# test2.net
KiCad netlist of a schematic drawn in Altium Designer
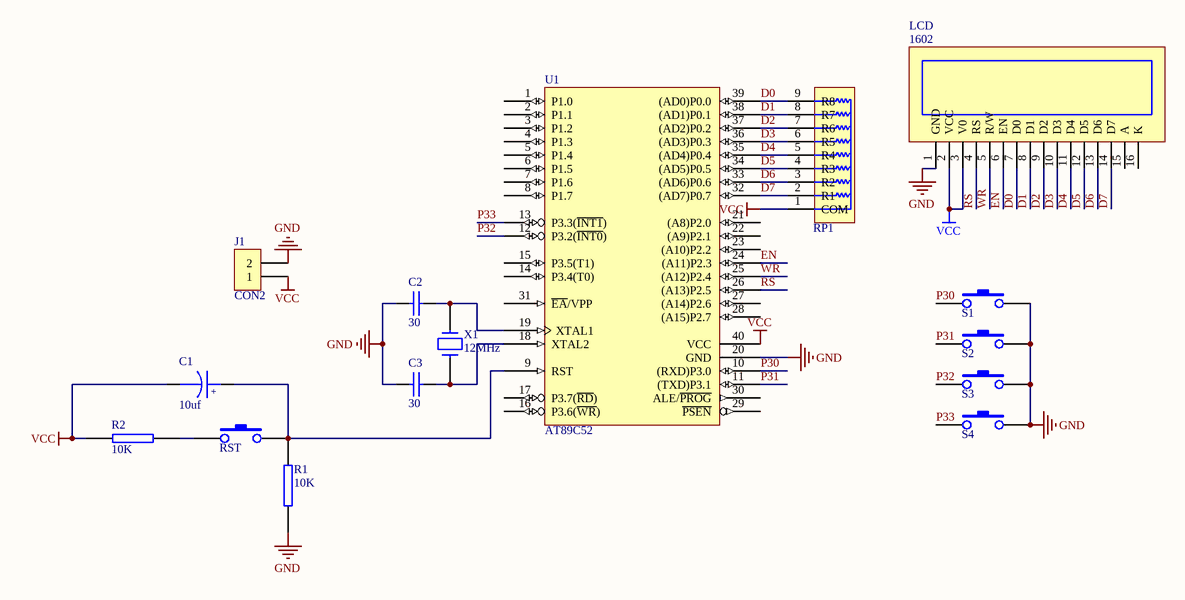
[diagram p0: test2.SchDoc]

(export (version "E")
  (design (tool "Eeschema 10.0.6"))
  (components
    (comp (ref "C1")
      (value "10uf")
      (footprint "C_SMT-5*5")
      (description "Capacitor")
      (libsource (lib "xinweidz") (part "电解电容"))
    )
    (comp (ref "C2")
      (value "30")
      (footprint "C0805")
      (description "Capacitor")
      (libsource (lib "*") (part "CAP"))
    )
    (comp (ref "C3")
      (value "30")
      (footprint "C0805")
      (description "Capacitor")
      (libsource (lib "*") (part "CAP"))
    )
    (comp (ref "J1")
      (value "CON2")
      (footprint "TC2")
      (description "Connector")
      (libsource (lib "51单片机最小系统.PcbDoc") (part "CON2"))
    )
    (comp (ref "LCD") (value "1602") (footprint "LCD1602") (libsource (lib "*") (part "LCM1602")))
    (comp (ref "R1") (value "10K") (footprint "C0805") (libsource (lib "*") (part "RES2")))
    (comp (ref "R2") (value "10K") (footprint "C0805") (libsource (lib "*") (part "RES2")))
    (comp (ref "RP1") (value "103") (footprint "R-9PIN") (libsource (lib "*") (part "RP8")))
    (comp (ref "RST")
      (value "SW-PB")
      (footprint "ANJIAN")
      (libsource (lib "51单片机最小系统.PcbDoc") (part "SW-PB"))
    )
    (comp (ref "S1") (value "SW-PB") (footprint "ANJIAN") (libsource (lib "51单片机最小系统.PcbDoc") (part "SW-PB")))
    (comp (ref "S2") (value "SW-PB") (footprint "ANJIAN") (libsource (lib "51单片机最小系统.PcbDoc") (part "SW-PB")))
    (comp (ref "S3") (value "SW-PB") (footprint "ANJIAN") (libsource (lib "51单片机最小系统.PcbDoc") (part "SW-PB")))
    (comp (ref "S4") (value "SW-PB") (footprint "ANJIAN") (libsource (lib "51单片机最小系统.PcbDoc") (part "SW-PB")))
    (comp (ref "U1")
      (value "AT89C52")
      (footprint "JINSUOZUO")
      (description "8-Bit Microcontroller with 4K Flash ROM")
      (libsource (lib "51单片机最小系统.PcbDoc") (part "AT89C51"))
    )
    (comp (ref "X1")
      (value "12MHz")
      (footprint "XTAL1")
      (description "Crystal")
      (libsource (lib "*") (part "CRYSTAL"))
    )
  )
  (nets
    (net (code "1") (name "/D0") (class "Default")
      (node (ref "LCD") (pin "7") (pinfunction "D0_7") (pintype "passive"))
      (node (ref "RP1") (pin "9") (pinfunction "R8_9") (pintype "passive"))
      (node (ref "U1") (pin "39") (pinfunction "(AD0)P0.0_39") (pintype "bidirectional"))
    )
    (net (code "2") (name "/D1") (class "Default")
      (node (ref "LCD") (pin "8") (pinfunction "D1_8") (pintype "passive"))
      (node (ref "RP1") (pin "8") (pinfunction "R7_8") (pintype "passive"))
      (node (ref "U1") (pin "38") (pinfunction "(AD1)P0.1_38") (pintype "bidirectional"))
    )
    (net (code "3") (name "/D2") (class "Default")
      (node (ref "LCD") (pin "9") (pinfunction "D2_9") (pintype "passive"))
      (node (ref "RP1") (pin "7") (pinfunction "R6_7") (pintype "passive"))
      (node (ref "U1") (pin "37") (pinfunction "(AD2)P0.2_37") (pintype "bidirectional"))
    )
    (net (code "4") (name "/D3") (class "Default")
      (node (ref "LCD") (pin "10") (pinfunction "D3_10") (pintype "passive"))
      (node (ref "RP1") (pin "6") (pinfunction "R5_6") (pintype "passive"))
      (node (ref "U1") (pin "36") (pinfunction "(AD3)P0.3_36") (pintype "bidirectional"))
    )
    (net (code "5") (name "/D4") (class "Default")
      (node (ref "LCD") (pin "11") (pinfunction "D4_11") (pintype "passive"))
      (node (ref "RP1") (pin "5") (pinfunction "R4_5") (pintype "passive"))
      (node (ref "U1") (pin "35") (pinfunction "(AD4)P0.4_35") (pintype "bidirectional"))
    )
    (net (code "6") (name "/D5") (class "Default")
      (node (ref "LCD") (pin "12") (pinfunction "D5_12") (pintype "passive"))
      (node (ref "RP1") (pin "4") (pinfunction "R3_4") (pintype "passive"))
      (node (ref "U1") (pin "34") (pinfunction "(AD5)P0.5_34") (pintype "bidirectional"))
    )
    (net (code "7") (name "/D6") (class "Default")
      (node (ref "LCD") (pin "13") (pinfunction "D6_13") (pintype "passive"))
      (node (ref "RP1") (pin "3") (pinfunction "R2_3") (pintype "passive"))
      (node (ref "U1") (pin "33") (pinfunction "(AD6)P0.6_33") (pintype "bidirectional"))
    )
    (net (code "8") (name "/D7") (class "Default")
      (node (ref "LCD") (pin "14") (pinfunction "D7_14") (pintype "passive"))
      (node (ref "RP1") (pin "2") (pinfunction "R1_2") (pintype "passive"))
      (node (ref "U1") (pin "32") (pinfunction "(AD7)P0.7_32") (pintype "bidirectional"))
    )
    (net (code "9") (name "/EN") (class "Default")
      (node (ref "LCD") (pin "6") (pinfunction "EN_6") (pintype "passive"))
      (node (ref "U1") (pin "24") (pinfunction "(A11)P2.3_24") (pintype "bidirectional"))
    )
    (net (code "10") (name "/P30") (class "Default")
      (node (ref "S1") (pin "1") (pinfunction "1_1") (pintype "passive"))
      (node (ref "U1") (pin "10") (pinfunction "(RXD)P3.0_10") (pintype "bidirectional"))
    )
    (net (code "11") (name "/P31") (class "Default")
      (node (ref "S2") (pin "1") (pinfunction "1_1") (pintype "passive"))
      (node (ref "U1") (pin "11") (pinfunction "(TXD)P3.1_11") (pintype "bidirectional"))
    )
    (net (code "12") (name "/P32") (class "Default")
      (node (ref "S3") (pin "1") (pinfunction "1_1") (pintype "passive"))
      (node (ref "U1") (pin "12") (pinfunction "P3.2(~{INT0})_12") (pintype "bidirectional"))
    )
    (net (code "13") (name "/P33") (class "Default")
      (node (ref "S4") (pin "1") (pinfunction "1_1") (pintype "passive"))
      (node (ref "U1") (pin "13") (pinfunction "P3.3(~{INT1})_13") (pintype "bidirectional"))
    )
    (net (code "14") (name "/RS") (class "Default")
      (node (ref "LCD") (pin "4") (pinfunction "RS_4") (pintype "passive"))
      (node (ref "U1") (pin "26") (pinfunction "(A13)P2.5_26") (pintype "bidirectional"))
    )
    (net (code "15") (name "/WR") (class "Default")
      (node (ref "LCD") (pin "5") (pinfunction "R/W_5") (pintype "passive"))
      (node (ref "U1") (pin "25") (pinfunction "(A12)P2.4_25") (pintype "bidirectional"))
    )
    (net (code "16") (name "GND") (class "Default")
      (node (ref "C2") (pin "2") (pinfunction "2_2") (pintype "passive"))
      (node (ref "C3") (pin "2") (pinfunction "2_2") (pintype "passive"))
      (node (ref "J1") (pin "2") (pinfunction "2_2") (pintype "passive"))
      (node (ref "LCD") (pin "1") (pinfunction "GND_1") (pintype "passive"))
      (node (ref "R1") (pin "2") (pinfunction "2_2") (pintype "passive"))
      (node (ref "S1") (pin "2") (pinfunction "2_2") (pintype "passive"))
      (node (ref "S2") (pin "2") (pinfunction "2_2") (pintype "passive"))
      (node (ref "S3") (pin "2") (pinfunction "2_2") (pintype "passive"))
      (node (ref "S4") (pin "2") (pinfunction "2_2") (pintype "passive"))
      (node (ref "U1") (pin "20") (pinfunction "GND_20") (pintype "power_in"))
    )
    (net (code "17") (name "Net-(R2-Pad2)") (class "Default")
      (node (ref "R2") (pin "2") (pinfunction "2_2") (pintype "passive"))
      (node (ref "RST") (pin "1") (pinfunction "1_1") (pintype "passive"))
    )
    (net (code "18") (name "Net-(U1-RST)") (class "Default")
      (node (ref "C1") (pin "2") (pinfunction "2_2") (pintype "passive"))
      (node (ref "R1") (pin "1") (pinfunction "1_1") (pintype "passive"))
      (node (ref "RST") (pin "2") (pinfunction "2_2") (pintype "passive"))
      (node (ref "U1") (pin "9") (pinfunction "RST_9") (pintype "input"))
    )
    (net (code "19") (name "Net-(U1-XTAL1)") (class "Default")
      (node (ref "C2") (pin "1") (pinfunction "1_1") (pintype "passive"))
      (node (ref "U1") (pin "19") (pinfunction "XTAL1_19") (pintype "input"))
      (node (ref "X1") (pin "1") (pinfunction "1_1") (pintype "passive"))
    )
    (net (code "20") (name "Net-(U1-XTAL2)") (class "Default")
      (node (ref "C3") (pin "1") (pinfunction "1_1") (pintype "passive"))
      (node (ref "U1") (pin "18") (pinfunction "XTAL2_18") (pintype "input"))
      (node (ref "X1") (pin "2") (pinfunction "2_2") (pintype "passive"))
    )
    (net (code "21") (name "VCC") (class "Default")
      (node (ref "C1") (pin "1") (pinfunction "1_1") (pintype "passive"))
      (node (ref "J1") (pin "1") (pinfunction "1_1") (pintype "passive"))
      (node (ref "LCD") (pin "2") (pinfunction "VCC_2") (pintype "passive"))
      (node (ref "LCD") (pin "3") (pinfunction "V0_3") (pintype "passive"))
      (node (ref "R2") (pin "1") (pinfunction "1_1") (pintype "passive"))
      (node (ref "RP1") (pin "1") (pinfunction "COM_1") (pintype "passive"))
      (node (ref "U1") (pin "40") (pinfunction "VCC_40") (pintype "power_in"))
    )
    (net (code "22") (name "unconnected-(LCD-A-Pad15)") (class "Default")
      (node (ref "LCD") (pin "15") (pinfunction "A_15") (pintype "passive"))
    )
    (net (code "23") (name "unconnected-(LCD-K-Pad16)") (class "Default")
      (node (ref "LCD") (pin "16") (pinfunction "K_16") (pintype "passive"))
    )
    (net (code "24") (name "unconnected-(U1-(A8)P2.0-Pad21)") (class "Default")
      (node (ref "U1") (pin "21") (pinfunction "(A8)P2.0_21") (pintype "bidirectional"))
    )
    (net (code "25") (name "unconnected-(U1-(A9)P2.1-Pad22)") (class "Default")
      (node (ref "U1") (pin "22") (pinfunction "(A9)P2.1_22") (pintype "bidirectional"))
    )
    (net (code "26") (name "unconnected-(U1-(A10)P2.2-Pad23)") (class "Default")
      (node (ref "U1") (pin "23") (pinfunction "(A10)P2.2_23") (pintype "bidirectional"))
    )
    (net (code "27") (name "unconnected-(U1-(A14)P2.6-Pad27)") (class "Default")
      (node (ref "U1") (pin "27") (pinfunction "(A14)P2.6_27") (pintype "bidirectional"))
    )
    (net (code "28") (name "unconnected-(U1-(A15)P2.7-Pad28)") (class "Default")
      (node (ref "U1") (pin "28") (pinfunction "(A15)P2.7_28") (pintype "bidirectional"))
    )
    (net (code "29") (name "unconnected-(U1-ALE{slash}~{PROG}-Pad30)") (class "Default")
      (node (ref "U1") (pin "30") (pinfunction "ALE/~{PROG}_30") (pintype "output"))
    )
    (net (code "30") (name "unconnected-(U1-P1.0-Pad1)") (class "Default")
      (node (ref "U1") (pin "1") (pinfunction "P1.0_1") (pintype "bidirectional"))
    )
    (net (code "31") (name "unconnected-(U1-P1.1-Pad2)") (class "Default")
      (node (ref "U1") (pin "2") (pinfunction "P1.1_2") (pintype "bidirectional"))
    )
    (net (code "32") (name "unconnected-(U1-P1.2-Pad3)") (class "Default")
      (node (ref "U1") (pin "3") (pinfunction "P1.2_3") (pintype "bidirectional"))
    )
    (net (code "33") (name "unconnected-(U1-P1.3-Pad4)") (class "Default")
      (node (ref "U1") (pin "4") (pinfunction "P1.3_4") (pintype "bidirectional"))
    )
    (net (code "34") (name "unconnected-(U1-P1.4-Pad5)") (class "Default")
      (node (ref "U1") (pin "5") (pinfunction "P1.4_5") (pintype "bidirectional"))
    )
    (net (code "35") (name "unconnected-(U1-P1.5-Pad6)") (class "Default")
      (node (ref "U1") (pin "6") (pinfunction "P1.5_6") (pintype "bidirectional"))
    )
    (net (code "36") (name "unconnected-(U1-P1.6-Pad7)") (class "Default")
      (node (ref "U1") (pin "7") (pinfunction "P1.6_7") (pintype "bidirectional"))
    )
    (net (code "37") (name "unconnected-(U1-P1.7-Pad8)") (class "Default")
      (node (ref "U1") (pin "8") (pinfunction "P1.7_8") (pintype "bidirectional"))
    )
    (net (code "38") (name "unconnected-(U1-P3.4(T0)-Pad14)") (class "Default")
      (node (ref "U1") (pin "14") (pinfunction "P3.4(T0)_14") (pintype "bidirectional"))
    )
    (net (code "39") (name "unconnected-(U1-P3.5(T1)-Pad15)") (class "Default")
      (node (ref "U1") (pin "15") (pinfunction "P3.5(T1)_15") (pintype "bidirectional"))
    )
    (net (code "40") (name "unconnected-(U1-P3.6(~{WR})-Pad16)") (class "Default")
      (node (ref "U1") (pin "16") (pinfunction "P3.6(~{WR})_16") (pintype "bidirectional"))
    )
    (net (code "41") (name "unconnected-(U1-P3.7(~{RD})-Pad17)") (class "Default")
      (node (ref "U1") (pin "17") (pinfunction "P3.7(~{RD})_17") (pintype "bidirectional"))
    )
    (net (code "42") (name "unconnected-(U1-~{EA}{slash}VPP-Pad31)") (class "Default")
      (node (ref "U1") (pin "31") (pinfunction "~{EA}/VPP_31") (pintype "input"))
    )
    (net (code "43") (name "unconnected-(U1-~{PSEN}-Pad29)") (class "Default")
      (node (ref "U1") (pin "29") (pinfunction "~{PSEN}_29") (pintype "output"))
    )
  )
)
